# Power.net
KiCad netlist of a schematic drawn in Altium Designer
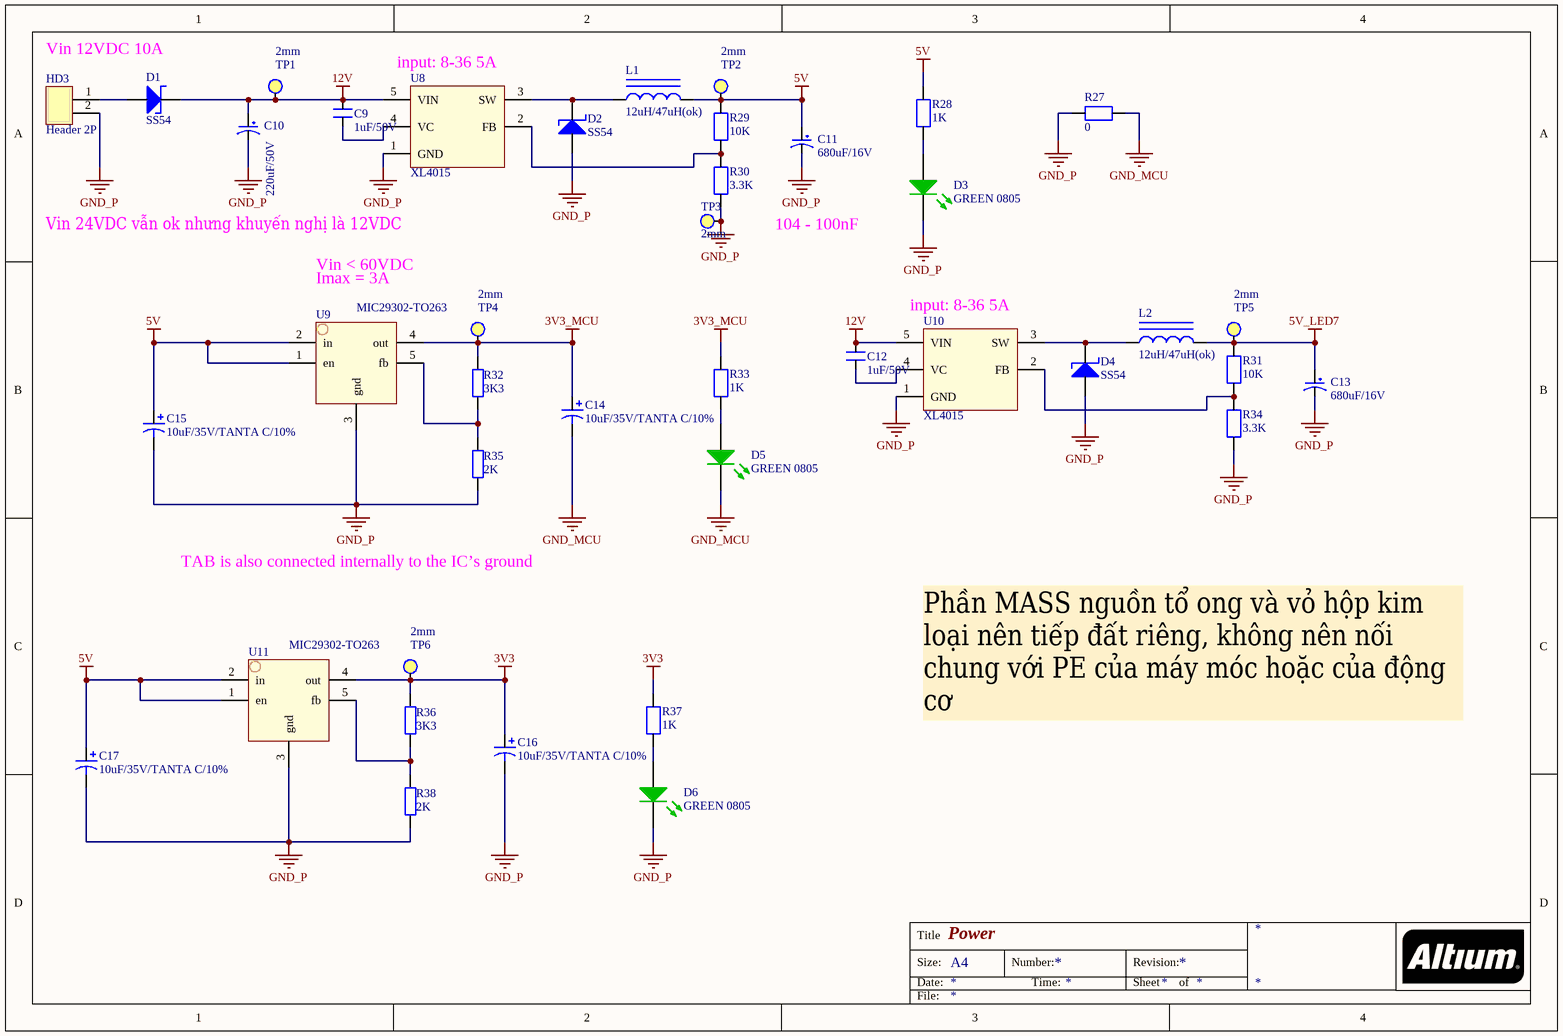
[diagram p0: Power.SchDoc]

(export (version "E")
  (design (tool "Eeschema 10.0.6"))
  (components
    (comp (ref "C9")
      (value "1uF/50V")
      (footprint "Cap Ceramic 0805 SMD")
      (libsource (lib "TanMy") (part "Cap Ceramic SMD"))
    )
    (comp (ref "C10")
      (value "220uF/50V")
      (footprint "CAP ALU CASE G SMD")
      (libsource (lib "TanMy") (part "Cap Alu SMD"))
    )
    (comp (ref "C11")
      (value "680uF/16V")
      (footprint "CAP ALU CASE G SMD")
      (libsource (lib "TanMy") (part "Cap Alu SMD"))
    )
    (comp (ref "C12")
      (value "1uF/50V")
      (footprint "Cap Ceramic 0805 SMD")
      (libsource (lib "TanMy") (part "Cap Ceramic SMD"))
    )
    (comp (ref "C13")
      (value "680uF/16V")
      (footprint "CAP ALU CASE G SMD")
      (libsource (lib "TanMy") (part "Cap Alu SMD"))
    )
    (comp (ref "C14")
      (value "10uF/35V/TANTA C/10%")
      (footprint "CAP TANT CASE C SMD")
      (description "Tantalum Capacitors - Solid SMD 25v 10uF 20%Tol Code C")
      (fields
        (field (name "MANUFACTURER") "Kyocera AVX")
        (field (name "MANUFACTURER PART NUMBER") "TAJB106M025RNJ")
      )
      (libsource (lib "GSHT_181013") (part "TAJB106M025RNJ"))
    )
    (comp (ref "C15")
      (value "10uF/35V/TANTA C/10%")
      (footprint "CAP TANT CASE C SMD")
      (description "Tantalum Capacitors - Solid SMD 25v 10uF 20%Tol Code C")
      (fields
        (field (name "MANUFACTURER") "Kyocera AVX")
        (field (name "MANUFACTURER PART NUMBER") "TAJB106M025RNJ")
      )
      (libsource (lib "GSHT_181013") (part "TAJB106M025RNJ"))
    )
    (comp (ref "C16")
      (value "10uF/35V/TANTA C/10%")
      (footprint "CAP TANT CASE C SMD")
      (description "Tantalum Capacitors - Solid SMD 25v 10uF 20%Tol Code C")
      (fields
        (field (name "MANUFACTURER") "Kyocera AVX")
        (field (name "MANUFACTURER PART NUMBER") "TAJB106M025RNJ")
      )
      (libsource (lib "GSHT_181013") (part "TAJB106M025RNJ"))
    )
    (comp (ref "C17")
      (value "10uF/35V/TANTA C/10%")
      (footprint "CAP TANT CASE C SMD")
      (description "Tantalum Capacitors - Solid SMD 25v 10uF 20%Tol Code C")
      (fields
        (field (name "MANUFACTURER") "Kyocera AVX")
        (field (name "MANUFACTURER PART NUMBER") "TAJB106M025RNJ")
      )
      (libsource (lib "GSHT_181013") (part "TAJB106M025RNJ"))
    )
    (comp (ref "D1")
      (value "SS54")
      (footprint "DO-214AB/SMC")
      (libsource (lib "TanMy") (part "Diode Schottky"))
    )
    (comp (ref "D2")
      (value "SS54")
      (footprint "DO-214AB/SMC")
      (libsource (lib "TanMy") (part "Diode Schottky"))
    )
    (comp (ref "D3")
      (value "GREEN 0805")
      (footprint "Led 0805G")
      (description "LED GREEN CLEAR 0603 SMD")
      (fields
        (field (name "MANUFACTURER") "Lite-On Inc.")
        (field (name "MANUFACTURER PART NUMBER") "LTST-C190KGKT")
      )
      (libsource (lib "lpson") (part "LED GREEN 0603"))
    )
    (comp (ref "D4")
      (value "SS54")
      (footprint "DO-214AB/SMC")
      (libsource (lib "TanMy") (part "Diode Schottky"))
    )
    (comp (ref "D5")
      (value "GREEN 0805")
      (footprint "Led 0805G")
      (description "LED GREEN CLEAR 0603 SMD")
      (fields
        (field (name "MANUFACTURER") "Lite-On Inc.")
        (field (name "MANUFACTURER PART NUMBER") "LTST-C190KGKT")
      )
      (libsource (lib "lpson") (part "LED GREEN 0603"))
    )
    (comp (ref "D6")
      (value "GREEN 0805")
      (footprint "Led 0805G")
      (description "LED GREEN CLEAR 0603 SMD")
      (fields
        (field (name "MANUFACTURER") "Lite-On Inc.")
        (field (name "MANUFACTURER PART NUMBER") "LTST-C190KGKT")
      )
      (libsource (lib "lpson") (part "LED GREEN 0603"))
    )
    (comp (ref "HD3")
      (value "Header 2P")
      (footprint "2EDGR-5.08-02P")
      (libsource (lib "TanMy") (part "Header 2P"))
    )
    (comp (ref "L1")
      (value "12uH/47uH(ok)")
      (footprint "POWER INDUCTOR")
      (description "CDRH127")
      (libsource (lib "TanMy") (part "Power Inductor"))
    )
    (comp (ref "L2")
      (value "12uH/47uH(ok)")
      (footprint "POWER INDUCTOR")
      (description "CDRH127")
      (libsource (lib "TanMy") (part "Power Inductor"))
    )
    (comp (ref "R27")
      (value "0")
      (footprint "Res 0805 SMD")
      (description "Resistor")
      (libsource (lib "TanMy") (part "Resistor"))
    )
    (comp (ref "R28")
      (value "1K")
      (footprint "Res 0805 SMD")
      (description "Resistor")
      (libsource (lib "TanMy") (part "Resistor"))
    )
    (comp (ref "R29")
      (value "10K")
      (footprint "Res 0805 SMD")
      (description "Resistor")
      (libsource (lib "TanMy") (part "Resistor"))
    )
    (comp (ref "R30")
      (value "3.3K")
      (footprint "Res 0805 SMD")
      (description "Resistor")
      (libsource (lib "TanMy") (part "Resistor"))
    )
    (comp (ref "R31")
      (value "10K")
      (footprint "Res 0805 SMD")
      (description "Resistor")
      (libsource (lib "TanMy") (part "Resistor"))
    )
    (comp (ref "R32")
      (value "3K3")
      (footprint "Res 0805 SMD")
      (description "Resistor SMD 0805")
      (fields (field (name "PUBLISHER") "Altium Limited"))
      (libsource (lib "NBBLib 14-03-2012") (part "R0805"))
    )
    (comp (ref "R33")
      (value "1K")
      (footprint "Res 0805 SMD")
      (description "Resistor")
      (libsource (lib "TanMy") (part "Resistor"))
    )
    (comp (ref "R34")
      (value "3.3K")
      (footprint "Res 0805 SMD")
      (description "Resistor")
      (libsource (lib "TanMy") (part "Resistor"))
    )
    (comp (ref "R35")
      (value "2K")
      (footprint "Res 0805 SMD")
      (description "Resistor SMD 0805")
      (fields (field (name "PUBLISHER") "Altium Limited"))
      (libsource (lib "NBBLib 14-03-2012") (part "R0805"))
    )
    (comp (ref "R36")
      (value "3K3")
      (footprint "Res 0805 SMD")
      (description "Resistor SMD 0805")
      (fields (field (name "PUBLISHER") "Altium Limited"))
      (libsource (lib "NBBLib 14-03-2012") (part "R0805"))
    )
    (comp (ref "R37")
      (value "1K")
      (footprint "Res 0805 SMD")
      (description "Resistor")
      (libsource (lib "TanMy") (part "Resistor"))
    )
    (comp (ref "R38")
      (value "2K")
      (footprint "Res 0805 SMD")
      (description "Resistor SMD 0805")
      (fields (field (name "PUBLISHER") "Altium Limited"))
      (libsource (lib "NBBLib 14-03-2012") (part "R0805"))
    )
    (comp (ref "TP1")
      (value "2mm")
      (footprint "Test Point 2mm")
      (description "Test Point SMD")
      (libsource (lib "TanMy") (part "Test Point"))
    )
    (comp (ref "TP2")
      (value "2mm")
      (footprint "Test Point 2mm")
      (description "Test Point SMD")
      (libsource (lib "TanMy") (part "Test Point"))
    )
    (comp (ref "TP3")
      (value "2mm")
      (footprint "Test Point 2mm")
      (description "Test Point SMD")
      (libsource (lib "TanMy") (part "Test Point"))
    )
    (comp (ref "TP4")
      (value "2mm")
      (footprint "Test Point 2mm")
      (description "Test Point SMD")
      (libsource (lib "TanMy") (part "Test Point"))
    )
    (comp (ref "TP5")
      (value "2mm")
      (footprint "Test Point 2mm")
      (description "Test Point SMD")
      (libsource (lib "TanMy") (part "Test Point"))
    )
    (comp (ref "TP6")
      (value "2mm")
      (footprint "Test Point 2mm")
      (description "Test Point SMD")
      (libsource (lib "TanMy") (part "Test Point"))
    )
    (comp (ref "U8")
      (value "XL4015")
      (footprint "TO-263-5P")
      (description "TO-263 5P")
      (libsource (lib "TanMy") (part "XL4015"))
    )
    (comp (ref "U9")
      (value "MIC29302-TO263")
      (footprint "MIC29302-TO263")
      (description "MIC29302 TO263\r\nHigh-Current Low-Dropout Regulators")
      (libsource (lib "PART2") (part "MIC29302"))
    )
    (comp (ref "U10")
      (value "XL4015")
      (footprint "TO-263-5P")
      (description "TO-263 5P")
      (libsource (lib "TanMy") (part "XL4015"))
    )
    (comp (ref "U11")
      (value "MIC29302-TO263")
      (footprint "MIC29302-TO263")
      (description "MIC29302 TO263\r\nHigh-Current Low-Dropout Regulators")
      (libsource (lib "PART2") (part "MIC29302"))
    )
  )
  (nets
    (net (code "1") (name "3V3") (class "Default")
      (node (ref "C16") (pin "1") (pinfunction "1_1") (pintype "passive"))
      (node (ref "R36") (pin "2") (pinfunction "2_2") (pintype "passive"))
      (node (ref "R37") (pin "2") (pinfunction "2_2") (pintype "passive"))
      (node (ref "TP6") (pin "1") (pinfunction "1_1") (pintype "passive"))
      (node (ref "U11") (pin "4") (pinfunction "out_4") (pintype "passive"))
    )
    (net (code "2") (name "3V3_MCU") (class "Default")
      (node (ref "C14") (pin "1") (pinfunction "1_1") (pintype "passive"))
      (node (ref "R32") (pin "2") (pinfunction "2_2") (pintype "passive"))
      (node (ref "R33") (pin "2") (pinfunction "2_2") (pintype "passive"))
      (node (ref "TP4") (pin "1") (pinfunction "1_1") (pintype "passive"))
      (node (ref "U9") (pin "4") (pinfunction "out_4") (pintype "passive"))
    )
    (net (code "3") (name "5V") (class "Default")
      (node (ref "C11") (pin "1") (pinfunction "1_1") (pintype "passive"))
      (node (ref "C15") (pin "1") (pinfunction "1_1") (pintype "passive"))
      (node (ref "C17") (pin "1") (pinfunction "1_1") (pintype "passive"))
      (node (ref "L1") (pin "2") (pinfunction "2_2") (pintype "passive"))
      (node (ref "R28") (pin "2") (pinfunction "2_2") (pintype "passive"))
      (node (ref "R29") (pin "2") (pinfunction "2_2") (pintype "passive"))
      (node (ref "TP2") (pin "1") (pinfunction "1_1") (pintype "passive"))
      (node (ref "U11") (pin "1") (pinfunction "en_1") (pintype "passive"))
      (node (ref "U11") (pin "2") (pinfunction "in_2") (pintype "passive"))
      (node (ref "U9") (pin "1") (pinfunction "en_1") (pintype "passive"))
      (node (ref "U9") (pin "2") (pinfunction "in_2") (pintype "passive"))
    )
    (net (code "4") (name "5V_LED7") (class "Default")
      (node (ref "C13") (pin "1") (pinfunction "1_1") (pintype "passive"))
      (node (ref "L2") (pin "2") (pinfunction "2_2") (pintype "passive"))
      (node (ref "R31") (pin "2") (pinfunction "2_2") (pintype "passive"))
      (node (ref "TP5") (pin "1") (pinfunction "1_1") (pintype "passive"))
    )
    (net (code "5") (name "12V") (class "Default")
      (node (ref "C10") (pin "1") (pinfunction "1_1") (pintype "passive"))
      (node (ref "C12") (pin "1") (pinfunction "1_1") (pintype "passive"))
      (node (ref "C9") (pin "1") (pinfunction "1_1") (pintype "passive"))
      (node (ref "D1") (pin "2") (pinfunction "K_2") (pintype "passive"))
      (node (ref "TP1") (pin "1") (pinfunction "1_1") (pintype "passive"))
      (node (ref "U10") (pin "5") (pinfunction "VIN_5") (pintype "passive"))
      (node (ref "U8") (pin "5") (pinfunction "VIN_5") (pintype "passive"))
    )
    (net (code "6") (name "GND_MCU") (class "Default")
      (node (ref "C14") (pin "2") (pinfunction "2_2") (pintype "passive"))
      (node (ref "D5") (pin "2") (pinfunction "K_2") (pintype "passive"))
      (node (ref "R27") (pin "1") (pinfunction "1_1") (pintype "passive"))
    )
    (net (code "7") (name "GND_P") (class "Default")
      (node (ref "C10") (pin "2") (pinfunction "2_2") (pintype "passive"))
      (node (ref "C11") (pin "2") (pinfunction "2_2") (pintype "passive"))
      (node (ref "C13") (pin "2") (pinfunction "2_2") (pintype "passive"))
      (node (ref "C15") (pin "2") (pinfunction "2_2") (pintype "passive"))
      (node (ref "C16") (pin "2") (pinfunction "2_2") (pintype "passive"))
      (node (ref "C17") (pin "2") (pinfunction "2_2") (pintype "passive"))
      (node (ref "D2") (pin "1") (pinfunction "A_1") (pintype "passive"))
      (node (ref "D3") (pin "2") (pinfunction "K_2") (pintype "passive"))
      (node (ref "D4") (pin "1") (pinfunction "A_1") (pintype "passive"))
      (node (ref "D6") (pin "2") (pinfunction "K_2") (pintype "passive"))
      (node (ref "HD3") (pin "2") (pinfunction "2_2") (pintype "passive"))
      (node (ref "R27") (pin "2") (pinfunction "2_2") (pintype "passive"))
      (node (ref "R30") (pin "1") (pinfunction "1_1") (pintype "passive"))
      (node (ref "R34") (pin "1") (pinfunction "1_1") (pintype "passive"))
      (node (ref "R35") (pin "1") (pinfunction "1_1") (pintype "passive"))
      (node (ref "R38") (pin "1") (pinfunction "1_1") (pintype "passive"))
      (node (ref "TP3") (pin "1") (pinfunction "1_1") (pintype "passive"))
      (node (ref "U10") (pin "1") (pinfunction "GND_1") (pintype "passive"))
      (node (ref "U11") (pin "3") (pinfunction "gnd_3") (pintype "passive"))
      (node (ref "U8") (pin "1") (pinfunction "GND_1") (pintype "passive"))
      (node (ref "U9") (pin "3") (pinfunction "gnd_3") (pintype "passive"))
    )
    (net (code "8") (name "Net-(D1-A)") (class "Default")
      (node (ref "D1") (pin "1") (pinfunction "A_1") (pintype "passive"))
      (node (ref "HD3") (pin "1") (pinfunction "1_1") (pintype "passive"))
    )
    (net (code "9") (name "Net-(D2-K)") (class "Default")
      (node (ref "D2") (pin "2") (pinfunction "K_2") (pintype "passive"))
      (node (ref "L1") (pin "1") (pinfunction "1_1") (pintype "passive"))
      (node (ref "U8") (pin "3") (pinfunction "SW_3") (pintype "passive"))
    )
    (net (code "10") (name "Net-(D3-A)") (class "Default")
      (node (ref "D3") (pin "1") (pinfunction "A_1") (pintype "passive"))
      (node (ref "R28") (pin "1") (pinfunction "1_1") (pintype "passive"))
    )
    (net (code "11") (name "Net-(D4-K)") (class "Default")
      (node (ref "D4") (pin "2") (pinfunction "K_2") (pintype "passive"))
      (node (ref "L2") (pin "1") (pinfunction "1_1") (pintype "passive"))
      (node (ref "U10") (pin "3") (pinfunction "SW_3") (pintype "passive"))
    )
    (net (code "12") (name "Net-(D5-A)") (class "Default")
      (node (ref "D5") (pin "1") (pinfunction "A_1") (pintype "passive"))
      (node (ref "R33") (pin "1") (pinfunction "1_1") (pintype "passive"))
    )
    (net (code "13") (name "Net-(D6-A)") (class "Default")
      (node (ref "D6") (pin "1") (pinfunction "A_1") (pintype "passive"))
      (node (ref "R37") (pin "1") (pinfunction "1_1") (pintype "passive"))
    )
    (net (code "14") (name "Net-(U8-FB)") (class "Default")
      (node (ref "R29") (pin "1") (pinfunction "1_1") (pintype "passive"))
      (node (ref "R30") (pin "2") (pinfunction "2_2") (pintype "passive"))
      (node (ref "U8") (pin "2") (pinfunction "FB_2") (pintype "passive"))
    )
    (net (code "15") (name "Net-(U8-VC)") (class "Default")
      (node (ref "C9") (pin "2") (pinfunction "2_2") (pintype "passive"))
      (node (ref "U8") (pin "4") (pinfunction "VC_4") (pintype "passive"))
    )
    (net (code "16") (name "Net-(U9-fb)") (class "Default")
      (node (ref "R32") (pin "1") (pinfunction "1_1") (pintype "passive"))
      (node (ref "R35") (pin "2") (pinfunction "2_2") (pintype "passive"))
      (node (ref "U9") (pin "5") (pinfunction "fb_5") (pintype "passive"))
    )
    (net (code "17") (name "Net-(U10-FB)") (class "Default")
      (node (ref "R31") (pin "1") (pinfunction "1_1") (pintype "passive"))
      (node (ref "R34") (pin "2") (pinfunction "2_2") (pintype "passive"))
      (node (ref "U10") (pin "2") (pinfunction "FB_2") (pintype "passive"))
    )
    (net (code "18") (name "Net-(U10-VC)") (class "Default")
      (node (ref "C12") (pin "2") (pinfunction "2_2") (pintype "passive"))
      (node (ref "U10") (pin "4") (pinfunction "VC_4") (pintype "passive"))
    )
    (net (code "19") (name "Net-(U11-fb)") (class "Default")
      (node (ref "R36") (pin "1") (pinfunction "1_1") (pintype "passive"))
      (node (ref "R38") (pin "2") (pinfunction "2_2") (pintype "passive"))
      (node (ref "U11") (pin "5") (pinfunction "fb_5") (pintype "passive"))
    )
  )
)
